# PCB-SENNHEISER_CHARGER_readout.net
KiCad netlist of a schematic drawn in EAGLE
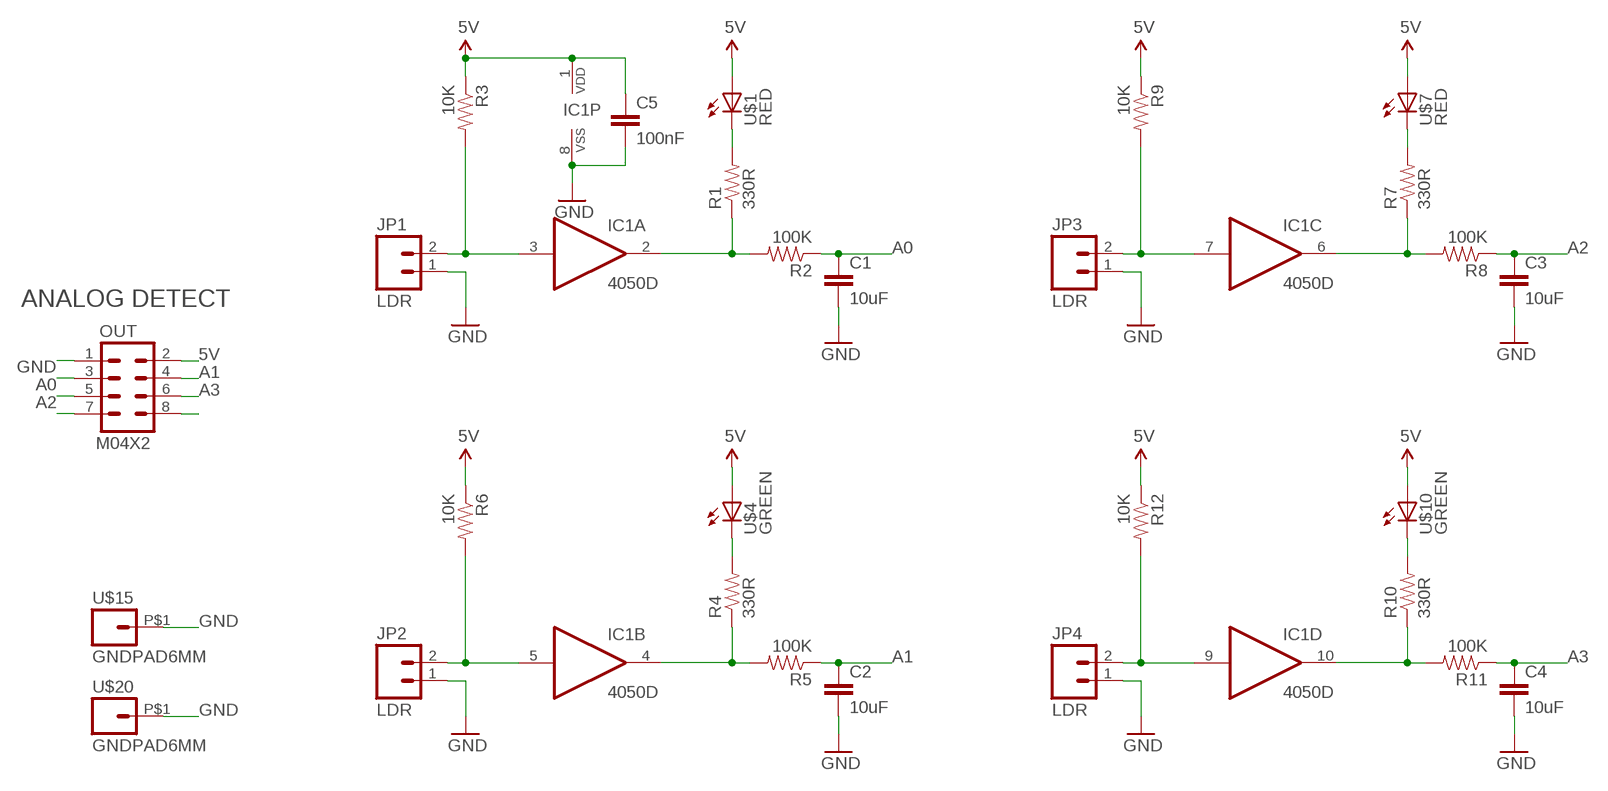
[diagram p0: schematic, sheet 1]

(export (version "E")
  (design (tool "Eeschema 10.0.6"))
  (components
    (comp (ref "C1")
      (value "10uF")
      (footprint "eagle-import:0603-CAP")
      (libsource (lib "eagle-import") (part "CAP0603-CAP"))
    )
    (comp (ref "C2")
      (value "10uF")
      (footprint "eagle-import:0603-CAP")
      (libsource (lib "eagle-import") (part "CAP0603-CAP"))
    )
    (comp (ref "C3")
      (value "10uF")
      (footprint "eagle-import:0603-CAP")
      (libsource (lib "eagle-import") (part "CAP0603-CAP"))
    )
    (comp (ref "C4")
      (value "10uF")
      (footprint "eagle-import:0603-CAP")
      (libsource (lib "eagle-import") (part "CAP0603-CAP"))
    )
    (comp (ref "C5")
      (value "100nF")
      (footprint "eagle-import:0603-CAP")
      (libsource (lib "eagle-import") (part "CAP0603-CAP"))
    )
    (comp (ref "IC1")
      (value "4050D")
      (footprint "eagle-import:SO16")
      (libsource (lib "eagle-import") (part "4050D"))
    )
    (comp (ref "JP1")
      (value "LDR")
      (footprint "eagle-import:1X02")
      (libsource (lib "eagle-import") (part "M02PTH"))
    )
    (comp (ref "JP2")
      (value "LDR")
      (footprint "eagle-import:1X02")
      (libsource (lib "eagle-import") (part "M02PTH"))
    )
    (comp (ref "JP3")
      (value "LDR")
      (footprint "eagle-import:1X02")
      (libsource (lib "eagle-import") (part "M02PTH"))
    )
    (comp (ref "JP4")
      (value "LDR")
      (footprint "eagle-import:1X02")
      (libsource (lib "eagle-import") (part "M02PTH"))
    )
    (comp (ref "OUT")
      (value "M04X2")
      (footprint "eagle-import:2X4")
      (libsource (lib "eagle-import") (part "M04X2"))
    )
    (comp (ref "R1")
      (value "330R")
      (footprint "eagle-import:0603-RES")
      (libsource (lib "eagle-import") (part "RESISTOR0603-RES"))
    )
    (comp (ref "R2")
      (value "100K")
      (footprint "eagle-import:0603-RES")
      (libsource (lib "eagle-import") (part "RESISTOR0603-RES"))
    )
    (comp (ref "R3")
      (value "10K")
      (footprint "eagle-import:0603-RES")
      (libsource (lib "eagle-import") (part "RESISTOR0603-RES"))
    )
    (comp (ref "R4")
      (value "330R")
      (footprint "eagle-import:0603-RES")
      (libsource (lib "eagle-import") (part "RESISTOR0603-RES"))
    )
    (comp (ref "R5")
      (value "100K")
      (footprint "eagle-import:0603-RES")
      (libsource (lib "eagle-import") (part "RESISTOR0603-RES"))
    )
    (comp (ref "R6")
      (value "10K")
      (footprint "eagle-import:0603-RES")
      (libsource (lib "eagle-import") (part "RESISTOR0603-RES"))
    )
    (comp (ref "R7")
      (value "330R")
      (footprint "eagle-import:0603-RES")
      (libsource (lib "eagle-import") (part "RESISTOR0603-RES"))
    )
    (comp (ref "R8")
      (value "100K")
      (footprint "eagle-import:0603-RES")
      (libsource (lib "eagle-import") (part "RESISTOR0603-RES"))
    )
    (comp (ref "R9")
      (value "10K")
      (footprint "eagle-import:0603-RES")
      (libsource (lib "eagle-import") (part "RESISTOR0603-RES"))
    )
    (comp (ref "R10")
      (value "330R")
      (footprint "eagle-import:0603-RES")
      (libsource (lib "eagle-import") (part "RESISTOR0603-RES"))
    )
    (comp (ref "R11")
      (value "100K")
      (footprint "eagle-import:0603-RES")
      (libsource (lib "eagle-import") (part "RESISTOR0603-RES"))
    )
    (comp (ref "R12")
      (value "10K")
      (footprint "eagle-import:0603-RES")
      (libsource (lib "eagle-import") (part "RESISTOR0603-RES"))
    )
    (comp (ref "U$1")
      (value "RED")
      (footprint "eagle-import:LED3MM")
      (libsource (lib "eagle-import") (part "LED3MM"))
    )
    (comp (ref "U$4")
      (value "GREEN")
      (footprint "eagle-import:LED3MM")
      (libsource (lib "eagle-import") (part "LED3MM"))
    )
    (comp (ref "U$7")
      (value "RED")
      (footprint "eagle-import:LED3MM")
      (libsource (lib "eagle-import") (part "LED3MM"))
    )
    (comp (ref "U$10")
      (value "GREEN")
      (footprint "eagle-import:LED3MM")
      (libsource (lib "eagle-import") (part "LED3MM"))
    )
    (comp (ref "U$15")
      (value "GNDPAD6MM")
      (footprint "eagle-import:3.2MMPAD6MM")
      (libsource (lib "eagle-import") (part "GNDPAD6MM"))
    )
    (comp (ref "U$20")
      (value "GNDPAD6MM")
      (footprint "eagle-import:3.2MMPAD6MM")
      (libsource (lib "eagle-import") (part "GNDPAD6MM"))
    )
  )
  (nets
    (net (code "1") (name "5V") (class "Default")
      (node (ref "C5") (pin "1") (pinfunction "1_1") (pintype "passive"))
      (node (ref "IC1") (pin "1") (pinfunction "VDD_1") (pintype "power_in"))
      (node (ref "OUT") (pin "2") (pinfunction "2_2") (pintype "passive"))
      (node (ref "R12") (pin "1") (pinfunction "1_1") (pintype "passive"))
      (node (ref "R3") (pin "1") (pinfunction "1_1") (pintype "passive"))
      (node (ref "R6") (pin "1") (pinfunction "1_1") (pintype "passive"))
      (node (ref "R9") (pin "1") (pinfunction "1_1") (pintype "passive"))
      (node (ref "U$1") (pin "A") (pinfunction "A_A") (pintype "passive"))
      (node (ref "U$10") (pin "A") (pinfunction "A_A") (pintype "passive"))
      (node (ref "U$4") (pin "A") (pinfunction "A_A") (pintype "passive"))
      (node (ref "U$7") (pin "A") (pinfunction "A_A") (pintype "passive"))
    )
    (net (code "2") (name "A0") (class "Default")
      (node (ref "C1") (pin "1") (pinfunction "1_1") (pintype "passive"))
      (node (ref "OUT") (pin "3") (pinfunction "3_3") (pintype "passive"))
      (node (ref "R2") (pin "1") (pinfunction "1_1") (pintype "passive"))
    )
    (net (code "3") (name "A1") (class "Default")
      (node (ref "C2") (pin "1") (pinfunction "1_1") (pintype "passive"))
      (node (ref "OUT") (pin "4") (pinfunction "4_4") (pintype "passive"))
      (node (ref "R5") (pin "1") (pinfunction "1_1") (pintype "passive"))
    )
    (net (code "4") (name "A2") (class "Default")
      (node (ref "C3") (pin "1") (pinfunction "1_1") (pintype "passive"))
      (node (ref "OUT") (pin "5") (pinfunction "5_5") (pintype "passive"))
      (node (ref "R8") (pin "1") (pinfunction "1_1") (pintype "passive"))
    )
    (net (code "5") (name "A3") (class "Default")
      (node (ref "C4") (pin "1") (pinfunction "1_1") (pintype "passive"))
      (node (ref "OUT") (pin "6") (pinfunction "6_6") (pintype "passive"))
      (node (ref "R11") (pin "1") (pinfunction "1_1") (pintype "passive"))
    )
    (net (code "6") (name "GND") (class "Default")
      (node (ref "C1") (pin "2") (pinfunction "2_2") (pintype "passive"))
      (node (ref "C2") (pin "2") (pinfunction "2_2") (pintype "passive"))
      (node (ref "C3") (pin "2") (pinfunction "2_2") (pintype "passive"))
      (node (ref "C4") (pin "2") (pinfunction "2_2") (pintype "passive"))
      (node (ref "C5") (pin "2") (pinfunction "2_2") (pintype "passive"))
      (node (ref "IC1") (pin "8") (pinfunction "VSS_8") (pintype "power_in"))
      (node (ref "JP1") (pin "1") (pinfunction "1_1") (pintype "passive"))
      (node (ref "JP2") (pin "1") (pinfunction "1_1") (pintype "passive"))
      (node (ref "JP3") (pin "1") (pinfunction "1_1") (pintype "passive"))
      (node (ref "JP4") (pin "1") (pinfunction "1_1") (pintype "passive"))
      (node (ref "OUT") (pin "1") (pinfunction "1_1") (pintype "passive"))
      (node (ref "U$15") (pin "P$1") (pinfunction "1_P$1") (pintype "passive"))
      (node (ref "U$20") (pin "P$1") (pinfunction "1_P$1") (pintype "passive"))
    )
    (net (code "7") (name "Net-(IC1A-I)") (class "Default")
      (node (ref "IC1") (pin "3") (pinfunction "I_3") (pintype "input"))
      (node (ref "JP1") (pin "2") (pinfunction "2_2") (pintype "passive"))
      (node (ref "R3") (pin "2") (pinfunction "2_2") (pintype "passive"))
    )
    (net (code "8") (name "Net-(IC1A-O)") (class "Default")
      (node (ref "IC1") (pin "2") (pinfunction "O_2") (pintype "output"))
      (node (ref "R1") (pin "1") (pinfunction "1_1") (pintype "passive"))
      (node (ref "R2") (pin "2") (pinfunction "2_2") (pintype "passive"))
    )
    (net (code "9") (name "Net-(IC1B-I)") (class "Default")
      (node (ref "IC1") (pin "5") (pinfunction "I_5") (pintype "input"))
      (node (ref "JP2") (pin "2") (pinfunction "2_2") (pintype "passive"))
      (node (ref "R6") (pin "2") (pinfunction "2_2") (pintype "passive"))
    )
    (net (code "10") (name "Net-(IC1B-O)") (class "Default")
      (node (ref "IC1") (pin "4") (pinfunction "O_4") (pintype "output"))
      (node (ref "R4") (pin "1") (pinfunction "1_1") (pintype "passive"))
      (node (ref "R5") (pin "2") (pinfunction "2_2") (pintype "passive"))
    )
    (net (code "11") (name "Net-(IC1C-I)") (class "Default")
      (node (ref "IC1") (pin "7") (pinfunction "I_7") (pintype "input"))
      (node (ref "JP3") (pin "2") (pinfunction "2_2") (pintype "passive"))
      (node (ref "R9") (pin "2") (pinfunction "2_2") (pintype "passive"))
    )
    (net (code "12") (name "Net-(IC1C-O)") (class "Default")
      (node (ref "IC1") (pin "6") (pinfunction "O_6") (pintype "output"))
      (node (ref "R7") (pin "1") (pinfunction "1_1") (pintype "passive"))
      (node (ref "R8") (pin "2") (pinfunction "2_2") (pintype "passive"))
    )
    (net (code "13") (name "Net-(IC1D-I)") (class "Default")
      (node (ref "IC1") (pin "9") (pinfunction "I_9") (pintype "input"))
      (node (ref "JP4") (pin "2") (pinfunction "2_2") (pintype "passive"))
      (node (ref "R12") (pin "2") (pinfunction "2_2") (pintype "passive"))
    )
    (net (code "14") (name "Net-(IC1D-O)") (class "Default")
      (node (ref "IC1") (pin "10") (pinfunction "O_10") (pintype "output"))
      (node (ref "R10") (pin "1") (pinfunction "1_1") (pintype "passive"))
      (node (ref "R11") (pin "2") (pinfunction "2_2") (pintype "passive"))
    )
    (net (code "15") (name "Net-(U$1-C)") (class "Default")
      (node (ref "R1") (pin "2") (pinfunction "2_2") (pintype "passive"))
      (node (ref "U$1") (pin "K") (pinfunction "C_K") (pintype "passive"))
    )
    (net (code "16") (name "Net-(U$4-C)") (class "Default")
      (node (ref "R4") (pin "2") (pinfunction "2_2") (pintype "passive"))
      (node (ref "U$4") (pin "K") (pinfunction "C_K") (pintype "passive"))
    )
    (net (code "17") (name "Net-(U$7-C)") (class "Default")
      (node (ref "R7") (pin "2") (pinfunction "2_2") (pintype "passive"))
      (node (ref "U$7") (pin "K") (pinfunction "C_K") (pintype "passive"))
    )
    (net (code "18") (name "Net-(U$10-C)") (class "Default")
      (node (ref "R10") (pin "2") (pinfunction "2_2") (pintype "passive"))
      (node (ref "U$10") (pin "K") (pinfunction "C_K") (pintype "passive"))
    )
    (net (code "19") (name "unconnected-(OUT-Pad7)") (class "Default")
      (node (ref "OUT") (pin "7") (pinfunction "7_7") (pintype "passive"))
    )
    (net (code "20") (name "unconnected-(OUT-Pad8)") (class "Default")
      (node (ref "OUT") (pin "8") (pinfunction "8_8") (pintype "passive"))
    )
  )
)
